# NE-CurrentSense-V3.net
KiCad netlist of a schematic drawn in Altium Designer
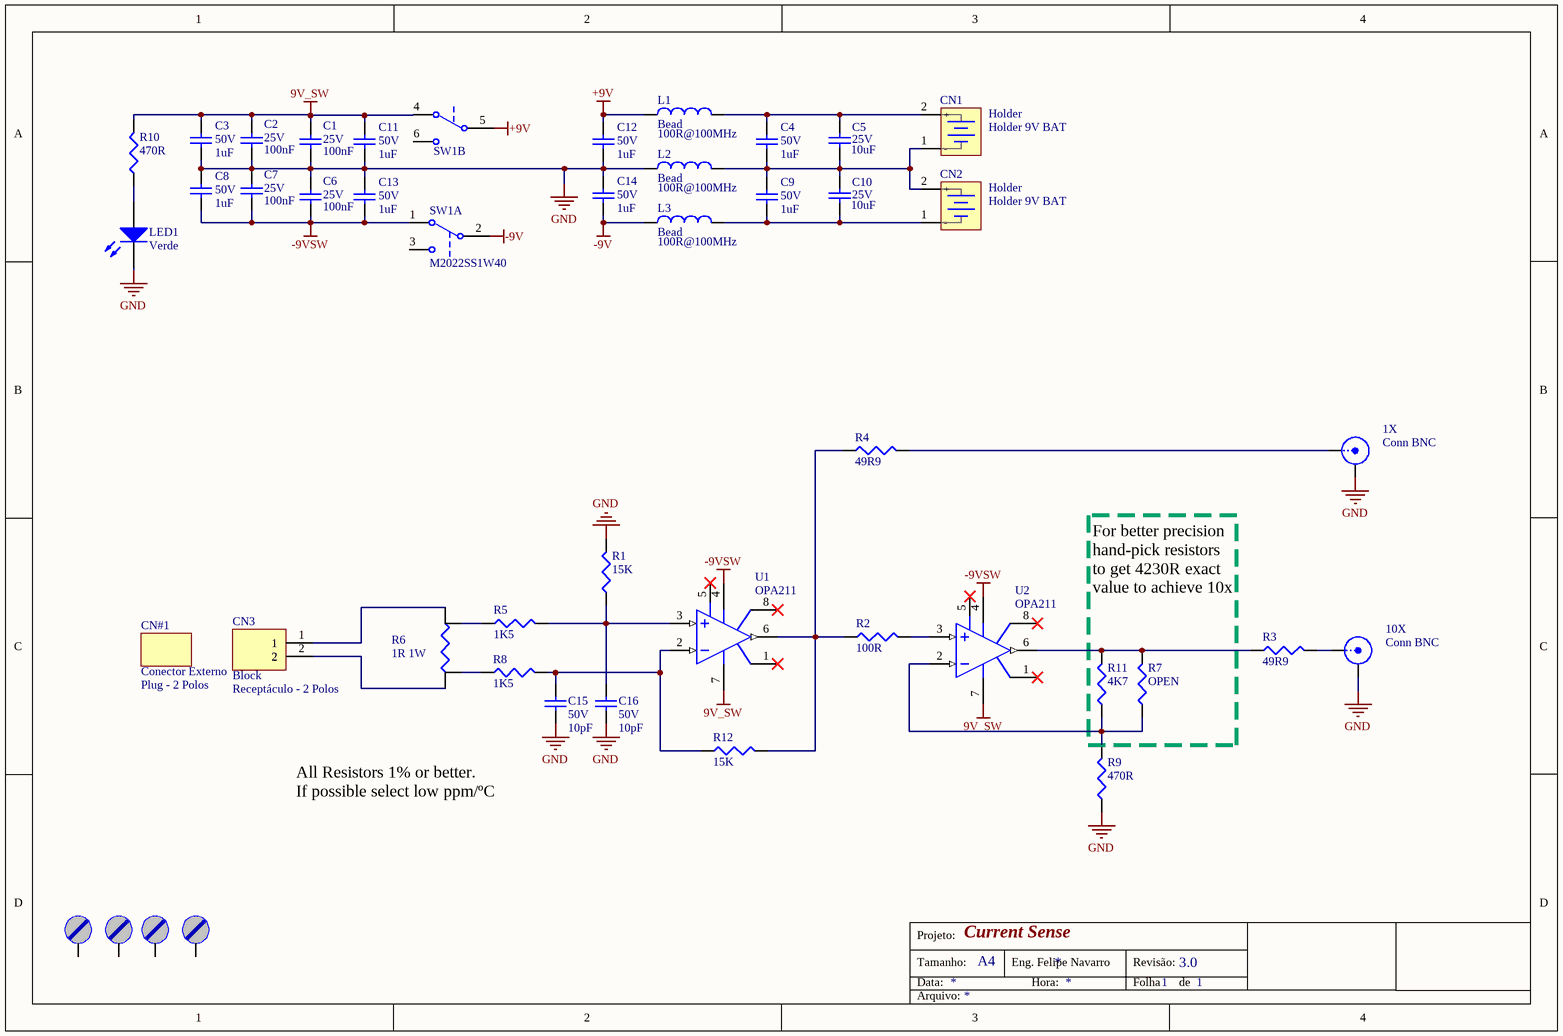
[diagram p0: NE-CurrentSense-V3.SchDoc]

(export (version "E")
  (design (tool "Eeschema 10.0.6"))
  (components
    (comp (ref "1X")
      (value "Conn BNC")
      (footprint "CONN BNC-JACK")
      (description "Conector BNC")
      (libsource (lib "NavarroCON") (part "Conn BNC"))
    )
    (comp (ref "10X")
      (value "Conn BNC")
      (footprint "CONN BNC-JACK")
      (description "Conector BNC")
      (libsource (lib "NavarroCON") (part "Conn BNC"))
    )
    (comp (ref "C1")
      (value "100nF")
      (footprint "CC0603")
      (description "Capacitor (Semiconductor SIM Model)")
      (fields (field (name "TENSÃO") "25V") (field (name "Comment") "Capacitor Cerâmico"))
      (libsource (lib "NavarroCAP") (part "Cap 100nF 25V 0603 X7R"))
    )
    (comp (ref "C2")
      (value "100nF")
      (footprint "CC0603")
      (description "Capacitor (Semiconductor SIM Model)")
      (fields (field (name "TENSÃO") "25V") (field (name "Comment") "Capacitor Cerâmico"))
      (libsource (lib "NavarroCAP") (part "Cap 100nF 25V 0603 X7R"))
    )
    (comp (ref "C3")
      (value "1uF")
      (footprint "CC0603")
      (description "Capacitor (Semiconductor SIM Model)")
      (fields (field (name "TENSÃO") "50V") (field (name "Comment") "Capacitor Cerâmico"))
      (libsource (lib "NavarroCAP") (part "Cap 1uF 50V 0603 X5R"))
    )
    (comp (ref "C4")
      (value "1uF")
      (footprint "CC0603")
      (description "Capacitor (Semiconductor SIM Model)")
      (fields (field (name "TENSÃO") "50V") (field (name "Comment") "Capacitor Cerâmico"))
      (libsource (lib "NavarroCAP") (part "Cap 1uF 50V 0603 X5R"))
    )
    (comp (ref "C5")
      (value "10uF")
      (footprint "CC0805")
      (description "Capacitor (Semiconductor SIM Model)")
      (fields (field (name "TENSÃO") "25V") (field (name "Comment") "Capacitor Cerâmico"))
      (libsource (lib "NavarroCAP") (part "Cap 10uF 25V 0805 X5R"))
    )
    (comp (ref "C6")
      (value "100nF")
      (footprint "CC0603")
      (description "Capacitor (Semiconductor SIM Model)")
      (fields (field (name "TENSÃO") "25V") (field (name "Comment") "Capacitor Cerâmico"))
      (libsource (lib "NavarroCAP") (part "Cap 100nF 25V 0603 X7R"))
    )
    (comp (ref "C7")
      (value "100nF")
      (footprint "CC0603")
      (description "Capacitor (Semiconductor SIM Model)")
      (fields (field (name "TENSÃO") "25V") (field (name "Comment") "Capacitor Cerâmico"))
      (libsource (lib "NavarroCAP") (part "Cap 100nF 25V 0603 X7R"))
    )
    (comp (ref "C8")
      (value "1uF")
      (footprint "CC0603")
      (description "Capacitor (Semiconductor SIM Model)")
      (fields (field (name "TENSÃO") "50V") (field (name "Comment") "Capacitor Cerâmico"))
      (libsource (lib "NavarroCAP") (part "Cap 1uF 50V 0603 X5R"))
    )
    (comp (ref "C9")
      (value "1uF")
      (footprint "CC0603")
      (description "Capacitor (Semiconductor SIM Model)")
      (fields (field (name "TENSÃO") "50V") (field (name "Comment") "Capacitor Cerâmico"))
      (libsource (lib "NavarroCAP") (part "Cap 1uF 50V 0603 X5R"))
    )
    (comp (ref "C10")
      (value "10uF")
      (footprint "CC0805")
      (description "Capacitor (Semiconductor SIM Model)")
      (fields (field (name "TENSÃO") "25V") (field (name "Comment") "Capacitor Cerâmico"))
      (libsource (lib "NavarroCAP") (part "Cap 10uF 25V 0805 X5R"))
    )
    (comp (ref "C11")
      (value "1uF")
      (footprint "CC0603")
      (description "Capacitor (Semiconductor SIM Model)")
      (fields (field (name "TENSÃO") "50V") (field (name "Comment") "Capacitor Cerâmico"))
      (libsource (lib "NavarroCAP") (part "Cap 1uF 50V 0603 X5R"))
    )
    (comp (ref "C12")
      (value "1uF")
      (footprint "CC0603")
      (description "Capacitor (Semiconductor SIM Model)")
      (fields (field (name "TENSÃO") "50V") (field (name "Comment") "Capacitor Cerâmico"))
      (libsource (lib "NavarroCAP") (part "Cap 1uF 50V 0603 X5R"))
    )
    (comp (ref "C13")
      (value "1uF")
      (footprint "CC0603")
      (description "Capacitor (Semiconductor SIM Model)")
      (fields (field (name "TENSÃO") "50V") (field (name "Comment") "Capacitor Cerâmico"))
      (libsource (lib "NavarroCAP") (part "Cap 1uF 50V 0603 X5R"))
    )
    (comp (ref "C14")
      (value "1uF")
      (footprint "CC0603")
      (description "Capacitor (Semiconductor SIM Model)")
      (fields (field (name "TENSÃO") "50V") (field (name "Comment") "Capacitor Cerâmico"))
      (libsource (lib "NavarroCAP") (part "Cap 1uF 50V 0603 X5R"))
    )
    (comp (ref "C15")
      (value "10pF")
      (footprint "CC0603")
      (description "Capacitor (Semiconductor SIM Model)")
      (fields (field (name "TENSÃO") "50V") (field (name "Comment") "Capacitor Cerâmico"))
      (libsource (lib "NavarroCAP") (part "Cap 10pF 50V 0603 NP0 5%"))
    )
    (comp (ref "C16")
      (value "10pF")
      (footprint "CC0603")
      (description "Capacitor (Semiconductor SIM Model)")
      (fields (field (name "TENSÃO") "50V") (field (name "Comment") "Capacitor Cerâmico"))
      (libsource (lib "NavarroCAP") (part "Cap 10pF 50V 0603 NP0 5%"))
    )
    (comp (ref "CN#1")
      (value "Conector Externo")
      (footprint "N/A")
      (description "Conector Plug")
      (fields (field (name "ALTIUM_VALUE") "Plug - 2 Polos"))
      (libsource (lib "NavarroCON") (part "Plug Block 2P 3.81mm"))
    )
    (comp (ref "CN1")
      (value "Holder")
      (footprint "BATTHOLDER-9V-BH9V-PC-ND")
      (fields (field (name "ALTIUM_VALUE") "Holder 9V BAT"))
      (libsource (lib "NavarroCON") (part "BattHolder 9V"))
    )
    (comp (ref "CN2")
      (value "Holder")
      (footprint "BATTHOLDER-9V-BH9V-PC-ND")
      (fields (field (name "ALTIUM_VALUE") "Holder 9V BAT"))
      (libsource (lib "NavarroCON") (part "BattHolder 9V"))
    )
    (comp (ref "CN3")
      (value "Block")
      (footprint "CONN BLOCK2 RCPT/H")
      (description "Conector Shrouded Block")
      (fields (field (name "ALTIUM_VALUE") "Receptáculo - 2 Polos"))
      (libsource (lib "NavarroCON") (part "SHRD Block 2P RCPT-H P3.81mm"))
    )
    (comp (ref "HOLE1")
      (value "Furo de Fixação")
      (footprint "Furo_M3")
      (description "Furo para parafuso")
      (libsource (lib "Navarro") (part "Parafuso"))
    )
    (comp (ref "HOLE3")
      (value "Furo de Fixação")
      (footprint "Furo_M3")
      (description "Furo para parafuso")
      (libsource (lib "Navarro") (part "Parafuso"))
    )
    (comp (ref "HOLE4")
      (value "Furo de Fixação")
      (footprint "Furo_M3")
      (description "Furo para parafuso")
      (libsource (lib "Navarro") (part "Parafuso"))
    )
    (comp (ref "HOLE5")
      (value "Furo de Fixação")
      (footprint "Furo_M3")
      (description "Furo para parafuso")
      (libsource (lib "Navarro") (part "Parafuso"))
    )
    (comp (ref "L1")
      (value "Bead")
      (footprint "CC0603")
      (fields (field (name "ALTIUM_VALUE") "100R@100MHz"))
      (libsource (lib "NavarroIND") (part "Bd 100R@100MHz 0603 2A"))
    )
    (comp (ref "L2")
      (value "Bead")
      (footprint "CC0603")
      (fields (field (name "ALTIUM_VALUE") "100R@100MHz"))
      (libsource (lib "NavarroIND") (part "Bd 100R@100MHz 0603 2A"))
    )
    (comp (ref "L3")
      (value "Bead")
      (footprint "CC0603")
      (fields (field (name "ALTIUM_VALUE") "100R@100MHz"))
      (libsource (lib "NavarroIND") (part "Bd 100R@100MHz 0603 2A"))
    )
    (comp (ref "LED1")
      (value "Verde")
      (footprint "LED-INDIC")
      (description "Typical RED, GREEN, YELLOW, AMBER GaAs LED")
      (fields (field (name "Comment") "LED"))
      (libsource (lib "Miscellaneous Devices") (part "LED2"))
    )
    (comp (ref "R1")
      (value "15K")
      (footprint "CC0603")
      (description "Resistor")
      (libsource (lib "NavarroRES") (part "Res 15K 0.1% 0603 1/10W"))
    )
    (comp (ref "R2")
      (value "100R")
      (footprint "CC0603")
      (description "Resistor")
      (libsource (lib "NavarroRES") (part "Res 100R 5% 0603 1/10W"))
    )
    (comp (ref "R3")
      (value "49R9")
      (footprint "CC0603")
      (description "Resistor")
      (libsource (lib "NavarroRES") (part "Res 49R9 1% 0603 1/10W"))
    )
    (comp (ref "R4")
      (value "49R9")
      (footprint "CC0603")
      (description "Resistor")
      (libsource (lib "NavarroRES") (part "Res 49R9 1% 0603 1/10W"))
    )
    (comp (ref "R5")
      (value "1K5")
      (footprint "CC0603")
      (description "Resistor")
      (libsource (lib "NavarroRES") (part "Res 1K5 1% 0603 1/10W"))
    )
    (comp (ref "R6")
      (value "1R 1W")
      (footprint "CC2516 - Wide Vishay")
      (description "Resistor")
      (libsource (lib "NavarroRES") (part "Res 1R 0.1% CC2516-Wide-4W 1W"))
    )
    (comp (ref "R7")
      (value "OPEN")
      (footprint "CC0603")
      (description "Resistor")
      (fields (field (name "Comment") "Resistor Open"))
      (libsource (lib "NavarroRES") (part "Res Open 0603"))
    )
    (comp (ref "R8")
      (value "1K5")
      (footprint "CC0603")
      (description "Resistor")
      (libsource (lib "NavarroRES") (part "Res 1K5 1% 0603 1/10W"))
    )
    (comp (ref "R9")
      (value "470R")
      (footprint "CC0603")
      (description "Resistor")
      (libsource (lib "NavarroRES") (part "Res 470R 5% 0603 1/10W"))
    )
    (comp (ref "R10")
      (value "470R")
      (footprint "CC0603")
      (description "Resistor")
      (libsource (lib "NavarroRES") (part "Res 470R 5% 0603 1/10W"))
    )
    (comp (ref "R11")
      (value "4K7")
      (footprint "CC0603")
      (description "Resistor")
      (libsource (lib "NavarroRES") (part "Res 4K7 1% 0603 1/10W"))
    )
    (comp (ref "R12")
      (value "15K")
      (footprint "CC0603")
      (description "Resistor")
      (libsource (lib "NavarroRES") (part "Res 15K 0.1% 0603 1/10W"))
    )
    (comp (ref "SW1")
      (value "M2022SS1W40")
      (footprint "SWITCH TOGGLE DPDT 6A 125V")
      (description "Double-Pole, Double-Throw Switch")
      (libsource (lib "Navarro") (part "SW-DPDT"))
    )
    (comp (ref "U1")
      (value "OPA211")
      (footprint "SOIC-8N")
      (description "Operational Amplifier")
      (libsource (lib "Navarro") (part "OPA211"))
    )
    (comp (ref "U2")
      (value "OPA211")
      (footprint "SOIC-8N")
      (description "Operational Amplifier")
      (libsource (lib "Navarro") (part "OPA211"))
    )
  )
  (nets
    (net (code "1") (name "+9V") (class "Default")
      (node (ref "C12") (pin "2") (pinfunction "2_2") (pintype "passive"))
      (node (ref "L1") (pin "1") (pinfunction "1_1") (pintype "passive"))
      (node (ref "SW1") (pin "5") (pinfunction "C2_5") (pintype "passive"))
    )
    (net (code "2") (name "-9V") (class "Default")
      (node (ref "C14") (pin "1") (pinfunction "1_1") (pintype "passive"))
      (node (ref "L3") (pin "1") (pinfunction "1_1") (pintype "passive"))
      (node (ref "SW1") (pin "2") (pinfunction "C1_2") (pintype "passive"))
    )
    (net (code "3") (name "-9VSW") (class "Default")
      (node (ref "C13") (pin "1") (pinfunction "1_1") (pintype "passive"))
      (node (ref "C6") (pin "1") (pinfunction "1_1") (pintype "passive"))
      (node (ref "C7") (pin "1") (pinfunction "1_1") (pintype "passive"))
      (node (ref "C8") (pin "1") (pinfunction "1_1") (pintype "passive"))
      (node (ref "SW1") (pin "1") (pinfunction "NC1_1") (pintype "passive"))
      (node (ref "U1") (pin "4") (pinfunction "V-_4") (pintype "power_in"))
      (node (ref "U2") (pin "4") (pinfunction "V-_4") (pintype "power_in"))
    )
    (net (code "4") (name "9V_SW") (class "Default")
      (node (ref "C1") (pin "2") (pinfunction "2_2") (pintype "passive"))
      (node (ref "C11") (pin "2") (pinfunction "2_2") (pintype "passive"))
      (node (ref "C2") (pin "2") (pinfunction "2_2") (pintype "passive"))
      (node (ref "C3") (pin "2") (pinfunction "2_2") (pintype "passive"))
      (node (ref "R10") (pin "2") (pinfunction "2_2") (pintype "passive"))
      (node (ref "SW1") (pin "4") (pinfunction "NC2_4") (pintype "passive"))
      (node (ref "U1") (pin "7") (pinfunction "V+_7") (pintype "power_in"))
      (node (ref "U2") (pin "7") (pinfunction "V+_7") (pintype "power_in"))
    )
    (net (code "5") (name "GND") (class "Default")
      (node (ref "10X") (pin "2") (pinfunction "Y_2") (pintype "passive"))
      (node (ref "1X") (pin "2") (pinfunction "Y_2") (pintype "passive"))
      (node (ref "C1") (pin "1") (pinfunction "1_1") (pintype "passive"))
      (node (ref "C11") (pin "1") (pinfunction "1_1") (pintype "passive"))
      (node (ref "C12") (pin "1") (pinfunction "1_1") (pintype "passive"))
      (node (ref "C13") (pin "2") (pinfunction "2_2") (pintype "passive"))
      (node (ref "C14") (pin "2") (pinfunction "2_2") (pintype "passive"))
      (node (ref "C15") (pin "1") (pinfunction "1_1") (pintype "passive"))
      (node (ref "C16") (pin "1") (pinfunction "1_1") (pintype "passive"))
      (node (ref "C2") (pin "1") (pinfunction "1_1") (pintype "passive"))
      (node (ref "C3") (pin "1") (pinfunction "1_1") (pintype "passive"))
      (node (ref "C6") (pin "2") (pinfunction "2_2") (pintype "passive"))
      (node (ref "C7") (pin "2") (pinfunction "2_2") (pintype "passive"))
      (node (ref "C8") (pin "2") (pinfunction "2_2") (pintype "passive"))
      (node (ref "L2") (pin "1") (pinfunction "1_1") (pintype "passive"))
      (node (ref "LED1") (pin "2") (pinfunction "K_2") (pintype "passive"))
      (node (ref "R1") (pin "2") (pinfunction "2_2") (pintype "passive"))
      (node (ref "R9") (pin "1") (pinfunction "1_1") (pintype "passive"))
    )
    (net (code "6") (name "Net-(1X-X)") (class "Default")
      (node (ref "1X") (pin "1") (pinfunction "X_1") (pintype "passive"))
      (node (ref "R4") (pin "2") (pinfunction "2_2") (pintype "passive"))
    )
    (net (code "7") (name "Net-(10X-X)") (class "Default")
      (node (ref "10X") (pin "1") (pinfunction "X_1") (pintype "passive"))
      (node (ref "R3") (pin "2") (pinfunction "2_2") (pintype "passive"))
    )
    (net (code "8") (name "Net-(CN1-+)") (class "Default")
      (node (ref "C4") (pin "2") (pinfunction "2_2") (pintype "passive"))
      (node (ref "C5") (pin "2") (pinfunction "2_2") (pintype "passive"))
      (node (ref "CN1") (pin "2") (pinfunction "+_2") (pintype "power_in"))
      (node (ref "L1") (pin "2") (pinfunction "2_2") (pintype "passive"))
    )
    (net (code "9") (name "Net-(CN1--)") (class "Default")
      (node (ref "C10") (pin "2") (pinfunction "2_2") (pintype "passive"))
      (node (ref "C4") (pin "1") (pinfunction "1_1") (pintype "passive"))
      (node (ref "C5") (pin "1") (pinfunction "1_1") (pintype "passive"))
      (node (ref "C9") (pin "2") (pinfunction "2_2") (pintype "passive"))
      (node (ref "CN1") (pin "1") (pinfunction "-_1") (pintype "power_in"))
      (node (ref "CN2") (pin "2") (pinfunction "+_2") (pintype "power_in"))
      (node (ref "L2") (pin "2") (pinfunction "2_2") (pintype "passive"))
    )
    (net (code "10") (name "Net-(CN2--)") (class "Default")
      (node (ref "C10") (pin "1") (pinfunction "1_1") (pintype "passive"))
      (node (ref "C9") (pin "1") (pinfunction "1_1") (pintype "passive"))
      (node (ref "CN2") (pin "1") (pinfunction "-_1") (pintype "power_in"))
      (node (ref "L3") (pin "2") (pinfunction "2_2") (pintype "passive"))
    )
    (net (code "11") (name "Net-(CN3-Pad1)") (class "Default")
      (node (ref "CN3") (pin "1") (pinfunction "1_1") (pintype "passive"))
      (node (ref "R6") (pin "3") (pinfunction "3_3") (pintype "passive"))
    )
    (net (code "12") (name "Net-(CN3-Pad2)") (class "Default")
      (node (ref "CN3") (pin "2") (pinfunction "2_2") (pintype "passive"))
      (node (ref "R6") (pin "1") (pinfunction "1_1") (pintype "passive"))
    )
    (net (code "13") (name "Net-(LED1-A)") (class "Default")
      (node (ref "LED1") (pin "1") (pinfunction "A_1") (pintype "passive"))
      (node (ref "R10") (pin "1") (pinfunction "1_1") (pintype "passive"))
    )
    (net (code "14") (name "Net-(R5-Pad1)") (class "Default")
      (node (ref "R5") (pin "1") (pinfunction "1_1") (pintype "passive"))
      (node (ref "R6") (pin "4") (pinfunction "4_4") (pintype "passive"))
    )
    (net (code "15") (name "Net-(R6-Pad2)") (class "Default")
      (node (ref "R6") (pin "2") (pinfunction "2_2") (pintype "passive"))
      (node (ref "R8") (pin "1") (pinfunction "1_1") (pintype "passive"))
    )
    (net (code "16") (name "Net-(U1-IN+)") (class "Default")
      (node (ref "C16") (pin "2") (pinfunction "2_2") (pintype "passive"))
      (node (ref "R1") (pin "1") (pinfunction "1_1") (pintype "passive"))
      (node (ref "R5") (pin "2") (pinfunction "2_2") (pintype "passive"))
      (node (ref "U1") (pin "3") (pinfunction "IN+_3") (pintype "input"))
    )
    (net (code "17") (name "Net-(U1-IN-)") (class "Default")
      (node (ref "C15") (pin "2") (pinfunction "2_2") (pintype "passive"))
      (node (ref "R12") (pin "1") (pinfunction "1_1") (pintype "passive"))
      (node (ref "R8") (pin "2") (pinfunction "2_2") (pintype "passive"))
      (node (ref "U1") (pin "2") (pinfunction "IN-_2") (pintype "input"))
    )
    (net (code "18") (name "Net-(U1-OUT)") (class "Default")
      (node (ref "R12") (pin "2") (pinfunction "2_2") (pintype "passive"))
      (node (ref "R2") (pin "1") (pinfunction "1_1") (pintype "passive"))
      (node (ref "R4") (pin "1") (pinfunction "1_1") (pintype "passive"))
      (node (ref "U1") (pin "6") (pinfunction "OUT_6") (pintype "output"))
    )
    (net (code "19") (name "Net-(U2-IN+)") (class "Default")
      (node (ref "R2") (pin "2") (pinfunction "2_2") (pintype "passive"))
      (node (ref "U2") (pin "3") (pinfunction "IN+_3") (pintype "input"))
    )
    (net (code "20") (name "Net-(U2-IN-)") (class "Default")
      (node (ref "R11") (pin "1") (pinfunction "1_1") (pintype "passive"))
      (node (ref "R7") (pin "1") (pinfunction "1_1") (pintype "passive"))
      (node (ref "R9") (pin "2") (pinfunction "2_2") (pintype "passive"))
      (node (ref "U2") (pin "2") (pinfunction "IN-_2") (pintype "input"))
    )
    (net (code "21") (name "Net-(U2-OUT)") (class "Default")
      (node (ref "R11") (pin "2") (pinfunction "2_2") (pintype "passive"))
      (node (ref "R3") (pin "1") (pinfunction "1_1") (pintype "passive"))
      (node (ref "R7") (pin "2") (pinfunction "2_2") (pintype "passive"))
      (node (ref "U2") (pin "6") (pinfunction "OUT_6") (pintype "output"))
    )
    (net (code "22") (name "unconnected-(HOLE1-PadX)") (class "Default")
      (node (ref "HOLE1") (pin "X") (pinfunction "X_X") (pintype "passive"))
    )
    (net (code "23") (name "unconnected-(HOLE3-PadX)") (class "Default")
      (node (ref "HOLE3") (pin "X") (pinfunction "X_X") (pintype "passive"))
    )
    (net (code "24") (name "unconnected-(HOLE4-PadX)") (class "Default")
      (node (ref "HOLE4") (pin "X") (pinfunction "X_X") (pintype "passive"))
    )
    (net (code "25") (name "unconnected-(HOLE5-PadX)") (class "Default")
      (node (ref "HOLE5") (pin "X") (pinfunction "X_X") (pintype "passive"))
    )
    (net (code "26") (name "unconnected-(SW1A-NO1-Pad3)") (class "Default")
      (node (ref "SW1") (pin "3") (pinfunction "NO1_3") (pintype "passive"))
    )
    (net (code "27") (name "unconnected-(SW1B-NO2-Pad6)") (class "Default")
      (node (ref "SW1") (pin "6") (pinfunction "NO2_6") (pintype "passive"))
    )
    (net (code "28") (name "unconnected-(U1-NC-Pad1)") (class "Default")
      (node (ref "U1") (pin "1") (pinfunction "NC_1") (pintype "passive+no_connect"))
    )
    (net (code "29") (name "unconnected-(U1-NC-Pad5)") (class "Default")
      (node (ref "U1") (pin "5") (pinfunction "NC_5") (pintype "passive+no_connect"))
    )
    (net (code "30") (name "unconnected-(U1-NC-Pad8)") (class "Default")
      (node (ref "U1") (pin "8") (pinfunction "NC_8") (pintype "passive+no_connect"))
    )
    (net (code "31") (name "unconnected-(U2-NC-Pad1)") (class "Default")
      (node (ref "U2") (pin "1") (pinfunction "NC_1") (pintype "passive+no_connect"))
    )
    (net (code "32") (name "unconnected-(U2-NC-Pad5)") (class "Default")
      (node (ref "U2") (pin "5") (pinfunction "NC_5") (pintype "passive+no_connect"))
    )
    (net (code "33") (name "unconnected-(U2-NC-Pad8)") (class "Default")
      (node (ref "U2") (pin "8") (pinfunction "NC_8") (pintype "passive+no_connect"))
    )
  )
)
